# LIC_V-00237-01.net
KiCad netlist of a schematic drawn in EAGLE
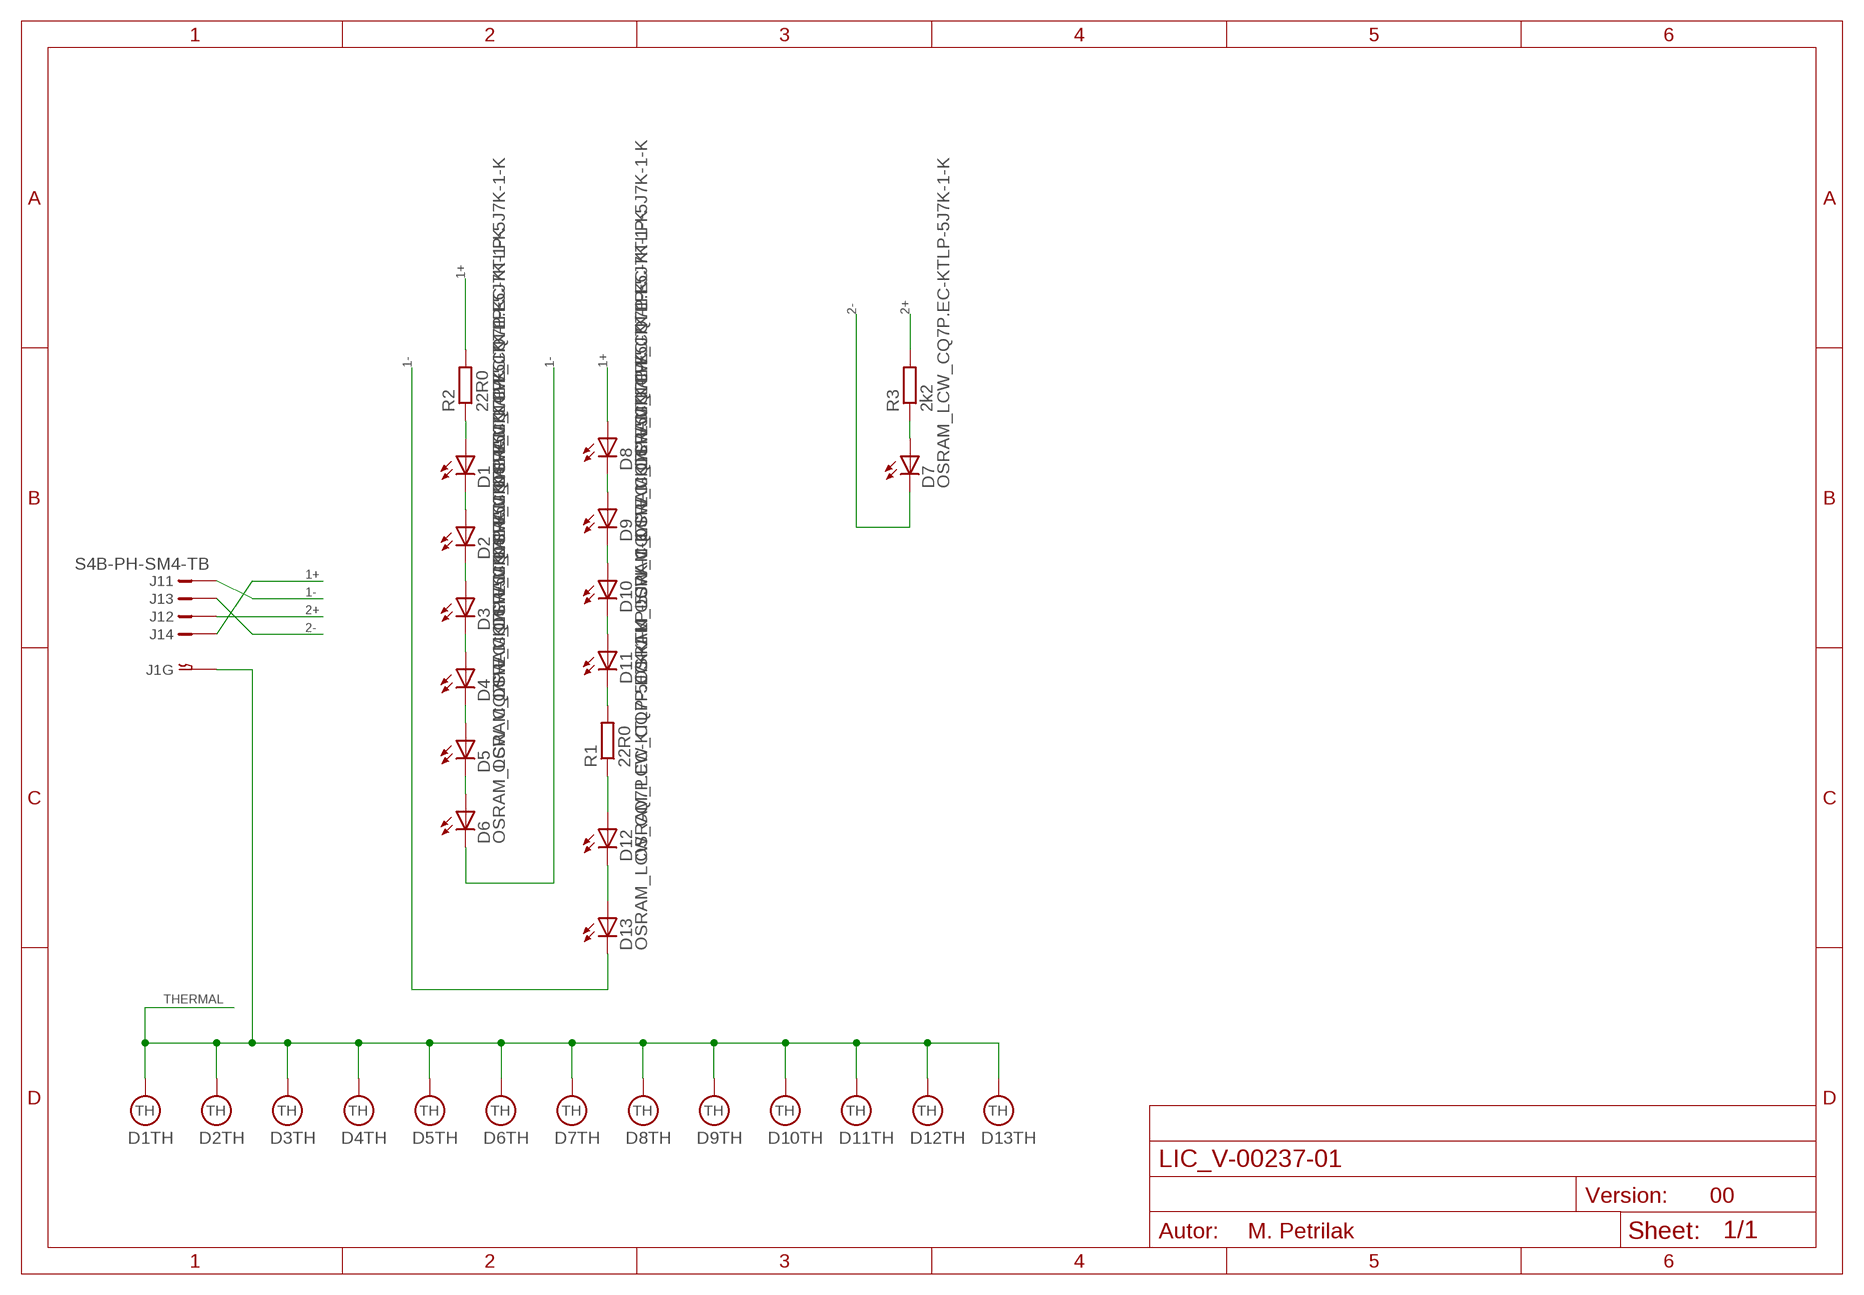
[diagram p0: schematic, sheet 1]

(export (version "E")
  (design (tool "Eeschema 10.0.6"))
  (components
    (comp (ref "D1")
      (value "OSRAM_LCW_CQ7P.EC-KTLP-5J7K-1-K")
      (footprint "eagle-import:OSRAM_LCW")
      (libsource (lib "eagle-import") (part "OSRAM_LCW_CQ7P.EC-KTLP-5J7K-1-K"))
    )
    (comp (ref "D2")
      (value "OSRAM_LCW_CQ7P.EC-KTLP-5J7K-1-K")
      (footprint "eagle-import:OSRAM_LCW")
      (libsource (lib "eagle-import") (part "OSRAM_LCW_CQ7P.EC-KTLP-5J7K-1-K"))
    )
    (comp (ref "D3")
      (value "OSRAM_LCW_CQ7P.EC-KTLP-5J7K-1-K")
      (footprint "eagle-import:OSRAM_LCW")
      (libsource (lib "eagle-import") (part "OSRAM_LCW_CQ7P.EC-KTLP-5J7K-1-K"))
    )
    (comp (ref "D4")
      (value "OSRAM_LCW_CQ7P.EC-KTLP-5J7K-1-K")
      (footprint "eagle-import:OSRAM_LCW")
      (libsource (lib "eagle-import") (part "OSRAM_LCW_CQ7P.EC-KTLP-5J7K-1-K"))
    )
    (comp (ref "D5")
      (value "OSRAM_LCW_CQ7P.EC-KTLP-5J7K-1-K")
      (footprint "eagle-import:OSRAM_LCW")
      (libsource (lib "eagle-import") (part "OSRAM_LCW_CQ7P.EC-KTLP-5J7K-1-K"))
    )
    (comp (ref "D6")
      (value "OSRAM_LCW_CQ7P.EC-KTLP-5J7K-1-K")
      (footprint "eagle-import:OSRAM_LCW")
      (libsource (lib "eagle-import") (part "OSRAM_LCW_CQ7P.EC-KTLP-5J7K-1-K"))
    )
    (comp (ref "D7")
      (value "OSRAM_LCW_CQ7P.EC-KTLP-5J7K-1-K")
      (footprint "eagle-import:OSRAM_LCW")
      (libsource (lib "eagle-import") (part "OSRAM_LCW_CQ7P.EC-KTLP-5J7K-1-K"))
    )
    (comp (ref "D8")
      (value "OSRAM_LCW_CQ7P.EC-KTLP-5J7K-1-K")
      (footprint "eagle-import:OSRAM_LCW")
      (libsource (lib "eagle-import") (part "OSRAM_LCW_CQ7P.EC-KTLP-5J7K-1-K"))
    )
    (comp (ref "D9")
      (value "OSRAM_LCW_CQ7P.EC-KTLP-5J7K-1-K")
      (footprint "eagle-import:OSRAM_LCW")
      (libsource (lib "eagle-import") (part "OSRAM_LCW_CQ7P.EC-KTLP-5J7K-1-K"))
    )
    (comp (ref "D10")
      (value "OSRAM_LCW_CQ7P.EC-KTLP-5J7K-1-K")
      (footprint "eagle-import:OSRAM_LCW")
      (libsource (lib "eagle-import") (part "OSRAM_LCW_CQ7P.EC-KTLP-5J7K-1-K"))
    )
    (comp (ref "D11")
      (value "OSRAM_LCW_CQ7P.EC-KTLP-5J7K-1-K")
      (footprint "eagle-import:OSRAM_LCW")
      (libsource (lib "eagle-import") (part "OSRAM_LCW_CQ7P.EC-KTLP-5J7K-1-K"))
    )
    (comp (ref "D12")
      (value "OSRAM_LCW_CQ7P.EC-KTLP-5J7K-1-K")
      (footprint "eagle-import:OSRAM_LCW")
      (libsource (lib "eagle-import") (part "OSRAM_LCW_CQ7P.EC-KTLP-5J7K-1-K"))
    )
    (comp (ref "D13")
      (value "OSRAM_LCW_CQ7P.EC-KTLP-5J7K-1-K")
      (footprint "eagle-import:OSRAM_LCW")
      (libsource (lib "eagle-import") (part "OSRAM_LCW_CQ7P.EC-KTLP-5J7K-1-K"))
    )
    (comp (ref "J1")
      (value "S4B-PH-SM4-TB")
      (footprint "eagle-import:S4B-PH-SM4-TB")
      (libsource (lib "eagle-import") (part "?4B-PH-SM4-TBS"))
    )
    (comp (ref "R1")
      (value "22R0")
      (footprint "eagle-import:R1206")
      (libsource (lib "eagle-import") (part "R-EU_R1206"))
    )
    (comp (ref "R2")
      (value "22R0")
      (footprint "eagle-import:R1206")
      (libsource (lib "eagle-import") (part "R-EU_R1206"))
    )
    (comp (ref "R3")
      (value "2k2")
      (footprint "eagle-import:R1206")
      (libsource (lib "eagle-import") (part "R-EU_R1206"))
    )
  )
  (nets
    (net (code "1") (name "/1+") (class "Default")
      (node (ref "D8") (pin "A") (pinfunction "A_A") (pintype "passive"))
      (node (ref "J1") (pin "4") (pinfunction "1_4") (pintype "passive"))
      (node (ref "R2") (pin "2") (pinfunction "2_2") (pintype "passive"))
    )
    (net (code "2") (name "/1-") (class "Default")
      (node (ref "D13") (pin "C") (pinfunction "C_C") (pintype "passive"))
      (node (ref "D6") (pin "C") (pinfunction "C_C") (pintype "passive"))
      (node (ref "J1") (pin "1") (pinfunction "1_1") (pintype "passive"))
    )
    (net (code "3") (name "/2+") (class "Default")
      (node (ref "J1") (pin "2") (pinfunction "1_2") (pintype "passive"))
      (node (ref "R3") (pin "2") (pinfunction "2_2") (pintype "passive"))
    )
    (net (code "4") (name "/2-") (class "Default")
      (node (ref "D7") (pin "C") (pinfunction "C_C") (pintype "passive"))
      (node (ref "J1") (pin "3") (pinfunction "1_3") (pintype "passive"))
    )
    (net (code "5") (name "/THERMAL") (class "Default")
      (node (ref "D1") (pin "THERMAL") (pinfunction "TH_THERMAL") (pintype "passive"))
      (node (ref "D10") (pin "THERMAL") (pinfunction "TH_THERMAL") (pintype "passive"))
      (node (ref "D11") (pin "THERMAL") (pinfunction "TH_THERMAL") (pintype "passive"))
      (node (ref "D12") (pin "THERMAL") (pinfunction "TH_THERMAL") (pintype "passive"))
      (node (ref "D13") (pin "THERMAL") (pinfunction "TH_THERMAL") (pintype "passive"))
      (node (ref "D2") (pin "THERMAL") (pinfunction "TH_THERMAL") (pintype "passive"))
      (node (ref "D3") (pin "THERMAL") (pinfunction "TH_THERMAL") (pintype "passive"))
      (node (ref "D4") (pin "THERMAL") (pinfunction "TH_THERMAL") (pintype "passive"))
      (node (ref "D5") (pin "THERMAL") (pinfunction "TH_THERMAL") (pintype "passive"))
      (node (ref "D6") (pin "THERMAL") (pinfunction "TH_THERMAL") (pintype "passive"))
      (node (ref "D7") (pin "THERMAL") (pinfunction "TH_THERMAL") (pintype "passive"))
      (node (ref "D8") (pin "THERMAL") (pinfunction "TH_THERMAL") (pintype "passive"))
      (node (ref "D9") (pin "THERMAL") (pinfunction "TH_THERMAL") (pintype "passive"))
      (node (ref "J1") (pin "GND1") (pinfunction "1_GND1") (pintype "passive"))
      (node (ref "J1") (pin "GND2") (pinfunction "1_GND2") (pintype "passive"))
    )
    (net (code "6") (name "Net-(D1-PadA)") (class "Default")
      (node (ref "D1") (pin "A") (pinfunction "A_A") (pintype "passive"))
      (node (ref "R2") (pin "1") (pinfunction "1_1") (pintype "passive"))
    )
    (net (code "7") (name "Net-(D1-PadC)") (class "Default")
      (node (ref "D1") (pin "C") (pinfunction "C_C") (pintype "passive"))
      (node (ref "D2") (pin "A") (pinfunction "A_A") (pintype "passive"))
    )
    (net (code "8") (name "Net-(D2-PadC)") (class "Default")
      (node (ref "D2") (pin "C") (pinfunction "C_C") (pintype "passive"))
      (node (ref "D3") (pin "A") (pinfunction "A_A") (pintype "passive"))
    )
    (net (code "9") (name "Net-(D3-PadC)") (class "Default")
      (node (ref "D3") (pin "C") (pinfunction "C_C") (pintype "passive"))
      (node (ref "D4") (pin "A") (pinfunction "A_A") (pintype "passive"))
    )
    (net (code "10") (name "Net-(D4-PadC)") (class "Default")
      (node (ref "D4") (pin "C") (pinfunction "C_C") (pintype "passive"))
      (node (ref "D5") (pin "A") (pinfunction "A_A") (pintype "passive"))
    )
    (net (code "11") (name "Net-(D5-PadC)") (class "Default")
      (node (ref "D5") (pin "C") (pinfunction "C_C") (pintype "passive"))
      (node (ref "D6") (pin "A") (pinfunction "A_A") (pintype "passive"))
    )
    (net (code "12") (name "Net-(D7-PadA)") (class "Default")
      (node (ref "D7") (pin "A") (pinfunction "A_A") (pintype "passive"))
      (node (ref "R3") (pin "1") (pinfunction "1_1") (pintype "passive"))
    )
    (net (code "13") (name "Net-(D8-PadC)") (class "Default")
      (node (ref "D8") (pin "C") (pinfunction "C_C") (pintype "passive"))
      (node (ref "D9") (pin "A") (pinfunction "A_A") (pintype "passive"))
    )
    (net (code "14") (name "Net-(D10-PadA)") (class "Default")
      (node (ref "D10") (pin "A") (pinfunction "A_A") (pintype "passive"))
      (node (ref "D9") (pin "C") (pinfunction "C_C") (pintype "passive"))
    )
    (net (code "15") (name "Net-(D10-PadC)") (class "Default")
      (node (ref "D10") (pin "C") (pinfunction "C_C") (pintype "passive"))
      (node (ref "D11") (pin "A") (pinfunction "A_A") (pintype "passive"))
    )
    (net (code "16") (name "Net-(D11-PadC)") (class "Default")
      (node (ref "D11") (pin "C") (pinfunction "C_C") (pintype "passive"))
      (node (ref "R1") (pin "2") (pinfunction "2_2") (pintype "passive"))
    )
    (net (code "17") (name "Net-(D12-PadA)") (class "Default")
      (node (ref "D12") (pin "A") (pinfunction "A_A") (pintype "passive"))
      (node (ref "R1") (pin "1") (pinfunction "1_1") (pintype "passive"))
    )
    (net (code "18") (name "Net-(D12-PadC)") (class "Default")
      (node (ref "D12") (pin "C") (pinfunction "C_C") (pintype "passive"))
      (node (ref "D13") (pin "A") (pinfunction "A_A") (pintype "passive"))
    )
  )
)
